# PG10__MCU.net
KiCad netlist of a schematic drawn in Altium Designer
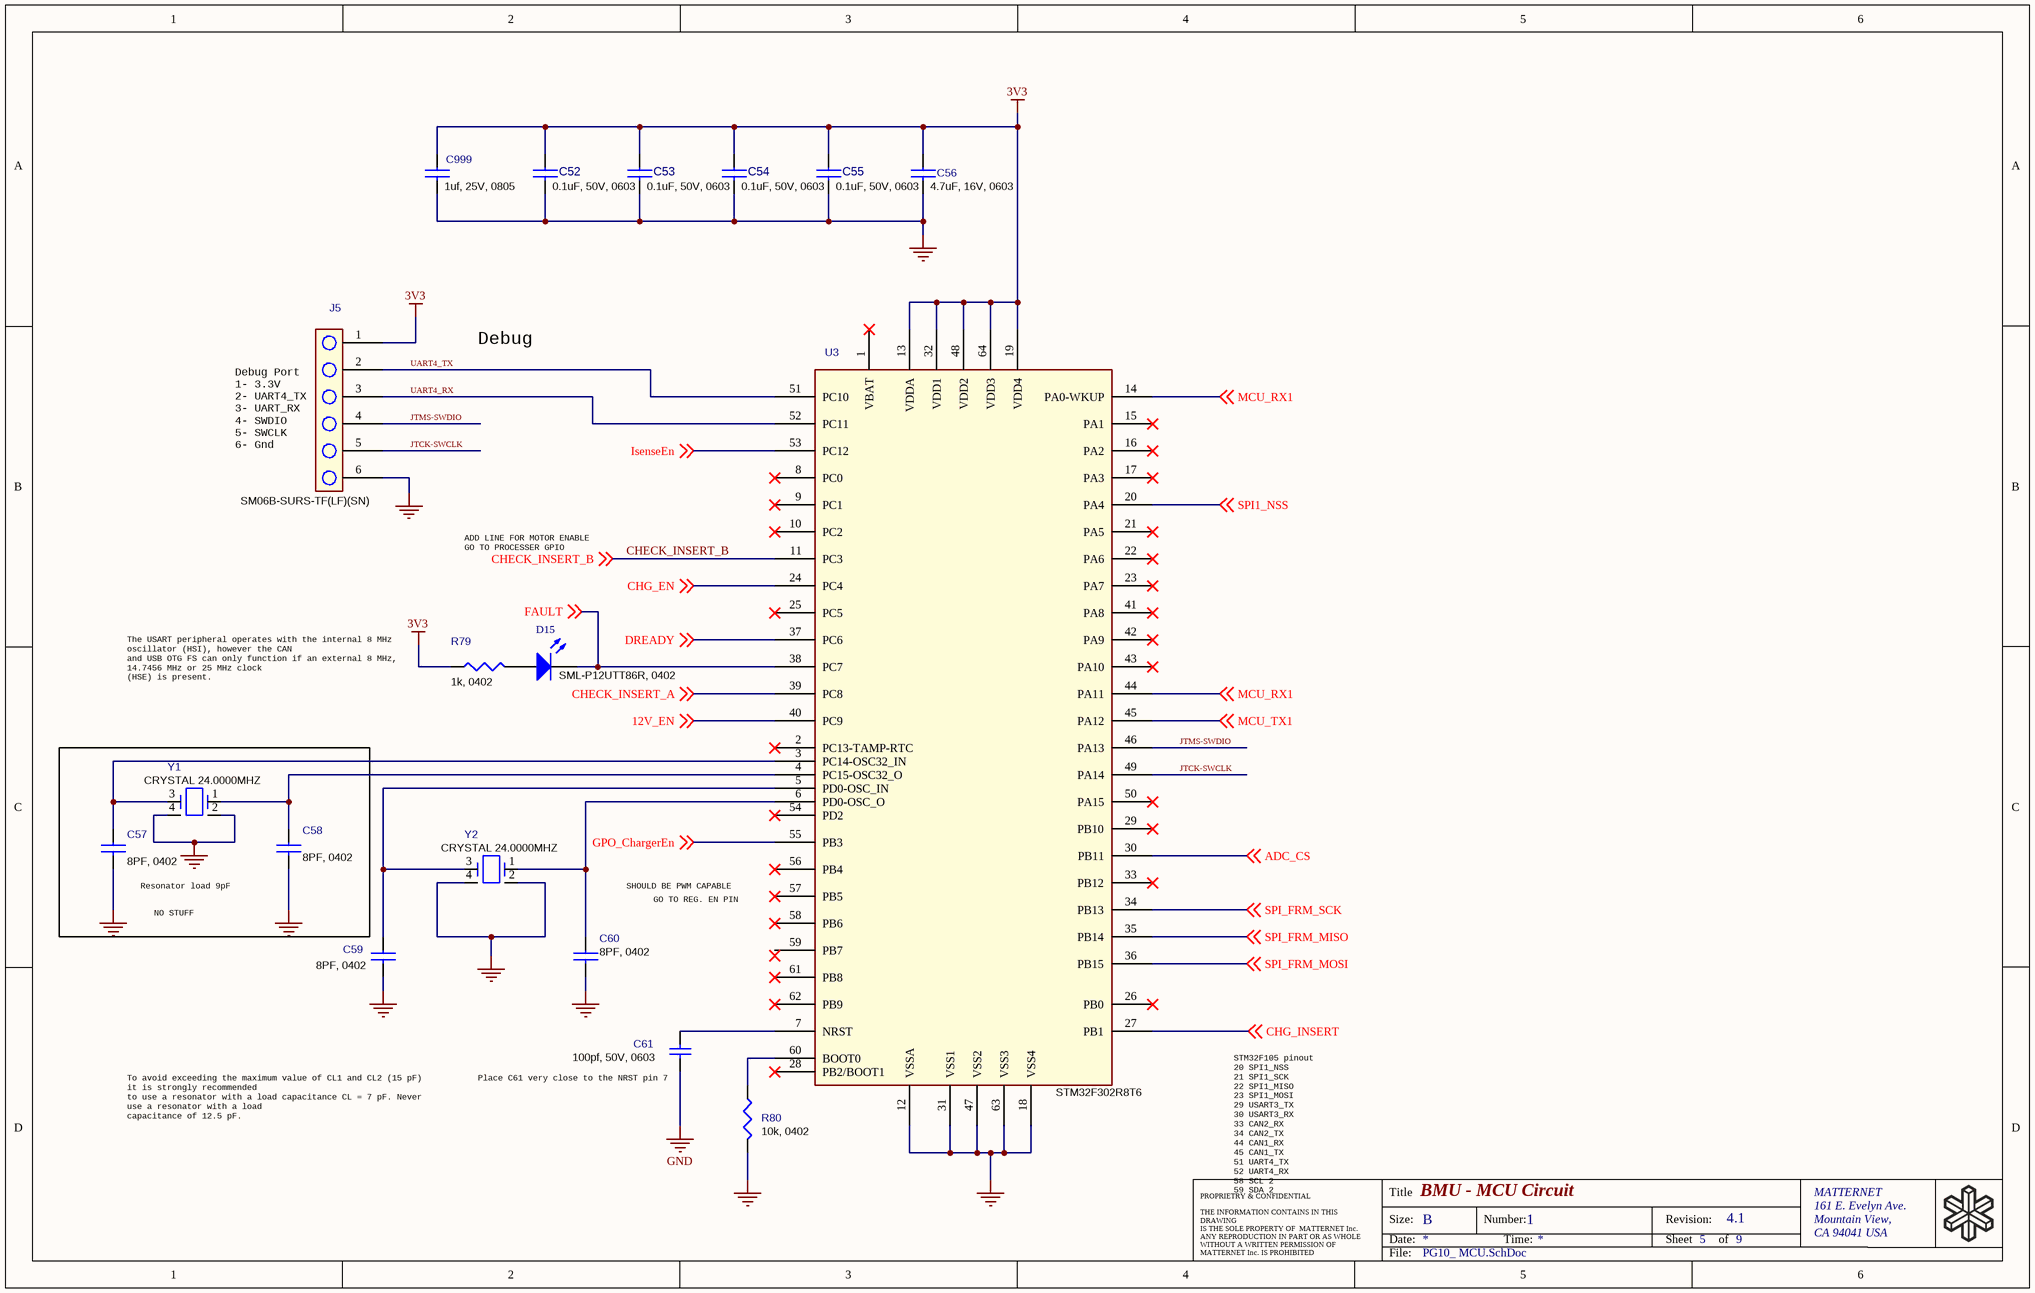
[diagram p0: PG10_ MCU.SchDoc]

(export (version "E")
  (design (tool "Eeschema 10.0.6"))
  (components
    (comp (ref "C52")
      (value "0.1uF, 50V, 0603")
      (footprint "C0603")
      (description "CAP CER 0.1UF 50V 10% X7R 0603")
      (fields
        (field (name "MANUFACTURER") "Murata")
        (field (name "MANUFACTURER PART NUMBER") "GCJ188R71E104KA12D")
      )
      (libsource (lib "*") (part "CAP-Generic-0603"))
    )
    (comp (ref "C53")
      (value "0.1uF, 50V, 0603")
      (footprint "C0603")
      (description "CAP CER 0.1UF 50V 10% X7R 0603")
      (fields
        (field (name "MANUFACTURER") "Murata")
        (field (name "MANUFACTURER PART NUMBER") "GCJ188R71E104KA12D")
      )
      (libsource (lib "*") (part "CAP-Generic-0603"))
    )
    (comp (ref "C54")
      (value "0.1uF, 50V, 0603")
      (footprint "C0603")
      (description "CAP CER 0.1UF 50V 10% X7R 0603")
      (fields
        (field (name "MANUFACTURER") "Murata")
        (field (name "MANUFACTURER PART NUMBER") "GCJ188R71E104KA12D")
      )
      (libsource (lib "*") (part "CAP-Generic-0603"))
    )
    (comp (ref "C55")
      (value "0.1uF, 50V, 0603")
      (footprint "C0603")
      (description "CAP CER 0.1UF 50V 10% X7R 0603")
      (fields
        (field (name "MANUFACTURER") "Murata")
        (field (name "MANUFACTURER PART NUMBER") "GCJ188R71E104KA12D")
      )
      (libsource (lib "*") (part "CAP-Generic-0603"))
    )
    (comp (ref "C56")
      (value "4.7uF, 16V, 0603")
      (footprint "C0805")
      (description "CAP CER 4.7UF 16V 10% X7R 0805")
      (fields
        (field (name "MANUFACTURER") "TDK")
        (field (name "MANUFACTURER PART NUMBER") "CGA4J3X7R1C475K125AE")
      )
      (libsource (lib "*") (part "CAP-Generic-0603"))
    )
    (comp (ref "C57")
      (value "8PF, 0402")
      (footprint "C0402")
      (description "CAP CER 8PF 50V C0G 0402")
      (fields
        (field (name "MANUFACTURER") "TDK")
        (field (name "MANUFACTURER PART NUMBER") "CGA2B2C0G1H080D050BA")
      )
      (libsource (lib "*") (part "CAP-Generic-0402"))
    )
    (comp (ref "C58")
      (value "8PF, 0402")
      (footprint "C0402")
      (description "CAP CER 8PF 50V C0G 0402")
      (fields
        (field (name "MANUFACTURER") "TDK")
        (field (name "MANUFACTURER PART NUMBER") "CGA2B2C0G1H080D050BA")
      )
      (libsource (lib "*") (part "CAP-Generic-0402"))
    )
    (comp (ref "C59")
      (value "8PF, 0402")
      (footprint "C0402")
      (description "CAP CER 8PF 50V C0G 0402")
      (fields
        (field (name "MANUFACTURER") "TDK")
        (field (name "MANUFACTURER PART NUMBER") "CGA2B2C0G1H080D050BA")
      )
      (libsource (lib "*") (part "CAP-Generic-0402"))
    )
    (comp (ref "C60")
      (value "8PF, 0402")
      (footprint "C0402")
      (description "CAP CER 8PF 50V C0G 0402")
      (fields
        (field (name "MANUFACTURER") "TDK")
        (field (name "MANUFACTURER PART NUMBER") "CGA2B2C0G1H080D050BA")
      )
      (libsource (lib "*") (part "CAP-Generic-0402"))
    )
    (comp (ref "C61")
      (value "100pf, 50V, 0603")
      (footprint "C0603")
      (description "CAP CER 100PF 50V NP0 0603")
      (fields
        (field (name "MANUFACTURER") "TDK")
        (field (name "MANUFACTURER PART NUMBER") "CGA3E2C0G1H101J080AE")
      )
      (libsource (lib "Miscellaneous Devices") (part "Cap"))
    )
    (comp (ref "C999")
      (value "1uf, 25V, 0805")
      (footprint "C0805")
      (description "CAP CER 1UF 25V X7R 0805")
      (fields
        (field (name "MANUFACTURER") "Murata")
        (field (name "MANUFACTURER PART NUMBER") "GCJ21BR71E105KA12L")
      )
      (libsource (lib "*") (part "CAP-Generic-0402"))
    )
    (comp (ref "D15")
      (value "SML-P12UTT86R, 0402")
      (footprint "D0402_1")
      (description "LED Uni-Color Red Chip LED 2-Pin 0402 T/R")
      (fields (field (name "MANUFACTURER") "Rohm") (field (name "MANUFACTURER PART NUMBER") "SML-P12U2TT86R"))
      (libsource (lib "Miscellaneous Devices") (part "LED0"))
    )
    (comp (ref "J5")
      (value "SM06B-SURS-TF(LF)(SN)")
      (footprint "0.8mm")
      (description "Headers & Wire Housings 6P SR UNSHRD HRD TIN OVER NI")
      (fields (field (name "MANUFACTURER") "JST"))
      (libsource (lib "*") (part "CONN-GENERIC-1X6"))
    )
    (comp (ref "R79")
      (value "1k, 0402")
      (footprint "R0402")
      (description "RES SMD 1K OHM 5% 1/16W 0402")
      (fields
        (field (name "MANUFACTURER") "Yageo")
        (field (name "MANUFACTURER PART NUMBER") "RC0402JR-071KL")
      )
      (libsource (lib "*") (part "R-Generic-0402"))
    )
    (comp (ref "R80")
      (value "10k, 0402")
      (footprint "R0402")
      (description "RES SMD 10K OHM 1% 1/16W 0402")
      (fields
        (field (name "MANUFACTURER") "Vishay Dale")
        (field (name "MANUFACTURER PART NUMBER") "CRCW040210K0FKTD")
      )
      (libsource (lib "Miscellaneous Devices") (part "R-Generic-0402"))
    )
    (comp (ref "U3")
      (value "STM32F302R8T6")
      (footprint "64LQFP")
      (description "MCU 32-bit STM32 ARM Cortex M4 RISC 128KB Flash 2.5V/3.3V 64-Pin LQFP Tray")
      (libsource (lib "*") (part "MCU-STM32F105RBT6-700-443"))
    )
    (comp (ref "Y1")
      (value "CRYSTAL 24.0000MHZ")
      (footprint "CRYSTAL_NX3225SA")
      (description "CRYSTAL 24.0000MHZ 8PF SMD")
      (fields
        (field (name "MANUFACTURER") "NDK")
        (field (name "MANUFACTURER PART NUMBER") "NX3225SA-24.000MHZ-STD-CSR-1")
      )
      (libsource (lib "*") (part "CRY-Generic"))
    )
    (comp (ref "Y2")
      (value "CRYSTAL 24.0000MHZ")
      (footprint "CRYSTAL_NX3225SA")
      (description "CRYSTAL 24.0000MHZ 8PF SMD")
      (fields
        (field (name "MANUFACTURER") "NDK")
        (field (name "MANUFACTURER PART NUMBER") "NX3225SA-24.000MHZ-STD-CSR-1")
      )
      (libsource (lib "*") (part "CRY-Generic"))
    )
  )
  (nets
    (net (code "1") (name "/JTCK-SWCLK") (class "Default")
      (node (ref "J5") (pin "5") (pinfunction "5_5") (pintype "passive"))
      (node (ref "U3") (pin "49") (pinfunction "PA14_49") (pintype "passive"))
    )
    (net (code "2") (name "/JTMS-SWDIO") (class "Default")
      (node (ref "J5") (pin "4") (pinfunction "4_4") (pintype "passive"))
      (node (ref "U3") (pin "46") (pinfunction "PA13_46") (pintype "passive"))
    )
    (net (code "3") (name "/UART4_RX") (class "Default")
      (node (ref "J5") (pin "3") (pinfunction "3_3") (pintype "passive"))
      (node (ref "U3") (pin "52") (pinfunction "PC11_52") (pintype "passive"))
    )
    (net (code "4") (name "/UART4_TX") (class "Default")
      (node (ref "J5") (pin "2") (pinfunction "2_2") (pintype "passive"))
      (node (ref "U3") (pin "51") (pinfunction "PC10_51") (pintype "passive"))
    )
    (net (code "5") (name "3V3") (class "Default")
      (node (ref "C52") (pin "1") (pinfunction "1_1") (pintype "passive"))
      (node (ref "C53") (pin "1") (pinfunction "1_1") (pintype "passive"))
      (node (ref "C54") (pin "1") (pinfunction "1_1") (pintype "passive"))
      (node (ref "C55") (pin "1") (pinfunction "1_1") (pintype "passive"))
      (node (ref "C56") (pin "1") (pinfunction "1_1") (pintype "passive"))
      (node (ref "C999") (pin "1") (pinfunction "1_1") (pintype "passive"))
      (node (ref "J5") (pin "1") (pinfunction "1_1") (pintype "passive"))
      (node (ref "R79") (pin "1") (pinfunction "1_1") (pintype "passive"))
      (node (ref "U3") (pin "13") (pinfunction "VDDA_13") (pintype "passive"))
      (node (ref "U3") (pin "19") (pinfunction "VDD4_19") (pintype "passive"))
      (node (ref "U3") (pin "32") (pinfunction "VDD1_32") (pintype "passive"))
      (node (ref "U3") (pin "48") (pinfunction "VDD2_48") (pintype "passive"))
      (node (ref "U3") (pin "64") (pinfunction "VDD3_64") (pintype "passive"))
    )
    (net (code "6") (name "12V_EN") (class "Default")
      (node (ref "U3") (pin "40") (pinfunction "PC9_40") (pintype "passive"))
    )
    (net (code "7") (name "ADC_CS") (class "Default")
      (node (ref "U3") (pin "30") (pinfunction "PB11_30") (pintype "passive"))
    )
    (net (code "8") (name "CHECK_INSERT_A") (class "Default")
      (node (ref "U3") (pin "39") (pinfunction "PC8_39") (pintype "passive"))
    )
    (net (code "9") (name "CHECK_INSERT_B") (class "Default")
      (node (ref "U3") (pin "11") (pinfunction "PC3_11") (pintype "passive"))
    )
    (net (code "10") (name "CHG_EN") (class "Default")
      (node (ref "U3") (pin "24") (pinfunction "PC4_24") (pintype "passive"))
    )
    (net (code "11") (name "CHG_INSERT") (class "Default")
      (node (ref "U3") (pin "27") (pinfunction "PB1_27") (pintype "passive"))
    )
    (net (code "12") (name "DREADY") (class "Default")
      (node (ref "U3") (pin "37") (pinfunction "PC6_37") (pintype "passive"))
    )
    (net (code "13") (name "FAULT") (class "Default")
      (node (ref "D15") (pin "2") (pinfunction "K_2") (pintype "passive"))
      (node (ref "U3") (pin "38") (pinfunction "PC7_38") (pintype "passive"))
    )
    (net (code "14") (name "GND") (class "Default")
      (node (ref "C52") (pin "2") (pinfunction "2_2") (pintype "passive"))
      (node (ref "C53") (pin "2") (pinfunction "2_2") (pintype "passive"))
      (node (ref "C54") (pin "2") (pinfunction "2_2") (pintype "passive"))
      (node (ref "C55") (pin "2") (pinfunction "2_2") (pintype "passive"))
      (node (ref "C56") (pin "2") (pinfunction "2_2") (pintype "passive"))
      (node (ref "C57") (pin "2") (pinfunction "2_2") (pintype "passive"))
      (node (ref "C58") (pin "2") (pinfunction "2_2") (pintype "passive"))
      (node (ref "C59") (pin "2") (pinfunction "2_2") (pintype "passive"))
      (node (ref "C60") (pin "2") (pinfunction "2_2") (pintype "passive"))
      (node (ref "C61") (pin "1") (pinfunction "1_1") (pintype "passive"))
      (node (ref "C999") (pin "2") (pinfunction "2_2") (pintype "passive"))
      (node (ref "J5") (pin "6") (pinfunction "6_6") (pintype "passive"))
      (node (ref "R80") (pin "2") (pinfunction "2_2") (pintype "passive"))
      (node (ref "U3") (pin "12") (pinfunction "VSSA_12") (pintype "passive"))
      (node (ref "U3") (pin "18") (pinfunction "VSS4_18") (pintype "passive"))
      (node (ref "U3") (pin "31") (pinfunction "VSS1_31") (pintype "passive"))
      (node (ref "U3") (pin "47") (pinfunction "VSS2_47") (pintype "passive"))
      (node (ref "U3") (pin "63") (pinfunction "VSS3_63") (pintype "passive"))
      (node (ref "Y1") (pin "2") (pinfunction "2_2") (pintype "passive"))
      (node (ref "Y1") (pin "4") (pinfunction "4_4") (pintype "passive"))
      (node (ref "Y2") (pin "2") (pinfunction "2_2") (pintype "passive"))
      (node (ref "Y2") (pin "4") (pinfunction "4_4") (pintype "passive"))
    )
    (net (code "15") (name "GPO_ChargerEn") (class "Default")
      (node (ref "U3") (pin "55") (pinfunction "PB3_55") (pintype "passive"))
    )
    (net (code "16") (name "IsenseEn") (class "Default")
      (node (ref "U3") (pin "53") (pinfunction "PC12_53") (pintype "passive"))
    )
    (net (code "17") (name "MCU_RX1") (class "Default")
      (node (ref "U3") (pin "14") (pinfunction "PA0-WKUP_14") (pintype "passive"))
      (node (ref "U3") (pin "44") (pinfunction "PA11_44") (pintype "passive"))
    )
    (net (code "18") (name "MCU_TX1") (class "Default")
      (node (ref "U3") (pin "45") (pinfunction "PA12_45") (pintype "passive"))
    )
    (net (code "19") (name "Net-(U3-BOOT0)") (class "Default")
      (node (ref "R80") (pin "1") (pinfunction "1_1") (pintype "passive"))
      (node (ref "U3") (pin "60") (pinfunction "BOOT0_60") (pintype "passive"))
    )
    (net (code "20") (name "Net-(U3-NRST)") (class "Default")
      (node (ref "C61") (pin "2") (pinfunction "2_2") (pintype "passive"))
      (node (ref "U3") (pin "7") (pinfunction "NRST_7") (pintype "passive"))
    )
    (net (code "21") (name "Net-(U3-PC14-OSC32_IN)") (class "Default")
      (node (ref "C57") (pin "1") (pinfunction "1_1") (pintype "passive"))
      (node (ref "U3") (pin "3") (pinfunction "PC14-OSC32_IN_3") (pintype "passive"))
      (node (ref "Y1") (pin "3") (pinfunction "3_3") (pintype "passive"))
    )
    (net (code "22") (name "Net-(U3-PC15-OSC32_O)") (class "Default")
      (node (ref "C58") (pin "1") (pinfunction "1_1") (pintype "passive"))
      (node (ref "U3") (pin "4") (pinfunction "PC15-OSC32_O_4") (pintype "passive"))
      (node (ref "Y1") (pin "1") (pinfunction "1_1") (pintype "passive"))
    )
    (net (code "23") (name "Net-(U3-PD0-OSC_IN)") (class "Default")
      (node (ref "C59") (pin "1") (pinfunction "1_1") (pintype "passive"))
      (node (ref "U3") (pin "5") (pinfunction "PD0-OSC_IN_5") (pintype "passive"))
      (node (ref "Y2") (pin "3") (pinfunction "3_3") (pintype "passive"))
    )
    (net (code "24") (name "Net-(U3-PD0-OSC_O)") (class "Default")
      (node (ref "C60") (pin "1") (pinfunction "1_1") (pintype "passive"))
      (node (ref "U3") (pin "6") (pinfunction "PD0-OSC_O_6") (pintype "passive"))
      (node (ref "Y2") (pin "1") (pinfunction "1_1") (pintype "passive"))
    )
    (net (code "25") (name "SPI1_NSS") (class "Default")
      (node (ref "U3") (pin "20") (pinfunction "PA4_20") (pintype "passive"))
    )
    (net (code "26") (name "SPI_FRM_MISO") (class "Default")
      (node (ref "U3") (pin "35") (pinfunction "PB14_35") (pintype "passive"))
    )
    (net (code "27") (name "SPI_FRM_MOSI") (class "Default")
      (node (ref "U3") (pin "36") (pinfunction "PB15_36") (pintype "passive"))
    )
    (net (code "28") (name "SPI_FRM_SCK") (class "Default")
      (node (ref "U3") (pin "34") (pinfunction "PB13_34") (pintype "passive"))
    )
    (net (code "29") (name "unconnected-(D15-A-Pad1)") (class "Default")
      (node (ref "D15") (pin "1") (pinfunction "A_1") (pintype "passive"))
    )
    (net (code "30") (name "unconnected-(R79-Pad2)") (class "Default")
      (node (ref "R79") (pin "2") (pinfunction "2_2") (pintype "passive"))
    )
    (net (code "31") (name "unconnected-(U3-PA1-Pad15)") (class "Default")
      (node (ref "U3") (pin "15") (pinfunction "PA1_15") (pintype "passive+no_connect"))
    )
    (net (code "32") (name "unconnected-(U3-PA2-Pad16)") (class "Default")
      (node (ref "U3") (pin "16") (pinfunction "PA2_16") (pintype "passive+no_connect"))
    )
    (net (code "33") (name "unconnected-(U3-PA3-Pad17)") (class "Default")
      (node (ref "U3") (pin "17") (pinfunction "PA3_17") (pintype "passive+no_connect"))
    )
    (net (code "34") (name "unconnected-(U3-PA5-Pad21)") (class "Default")
      (node (ref "U3") (pin "21") (pinfunction "PA5_21") (pintype "passive+no_connect"))
    )
    (net (code "35") (name "unconnected-(U3-PA6-Pad22)") (class "Default")
      (node (ref "U3") (pin "22") (pinfunction "PA6_22") (pintype "passive+no_connect"))
    )
    (net (code "36") (name "unconnected-(U3-PA7-Pad23)") (class "Default")
      (node (ref "U3") (pin "23") (pinfunction "PA7_23") (pintype "passive+no_connect"))
    )
    (net (code "37") (name "unconnected-(U3-PA8-Pad41)") (class "Default")
      (node (ref "U3") (pin "41") (pinfunction "PA8_41") (pintype "passive+no_connect"))
    )
    (net (code "38") (name "unconnected-(U3-PA9-Pad42)") (class "Default")
      (node (ref "U3") (pin "42") (pinfunction "PA9_42") (pintype "passive+no_connect"))
    )
    (net (code "39") (name "unconnected-(U3-PA10-Pad43)") (class "Default")
      (node (ref "U3") (pin "43") (pinfunction "PA10_43") (pintype "passive+no_connect"))
    )
    (net (code "40") (name "unconnected-(U3-PA15-Pad50)") (class "Default")
      (node (ref "U3") (pin "50") (pinfunction "PA15_50") (pintype "passive+no_connect"))
    )
    (net (code "41") (name "unconnected-(U3-PB0-Pad26)") (class "Default")
      (node (ref "U3") (pin "26") (pinfunction "PB0_26") (pintype "passive+no_connect"))
    )
    (net (code "42") (name "unconnected-(U3-PB2{slash}BOOT1-Pad28)") (class "Default")
      (node (ref "U3") (pin "28") (pinfunction "PB2/BOOT1_28") (pintype "passive+no_connect"))
    )
    (net (code "43") (name "unconnected-(U3-PB4-Pad56)") (class "Default")
      (node (ref "U3") (pin "56") (pinfunction "PB4_56") (pintype "passive+no_connect"))
    )
    (net (code "44") (name "unconnected-(U3-PB5-Pad57)") (class "Default")
      (node (ref "U3") (pin "57") (pinfunction "PB5_57") (pintype "passive+no_connect"))
    )
    (net (code "45") (name "unconnected-(U3-PB6-Pad58)") (class "Default")
      (node (ref "U3") (pin "58") (pinfunction "PB6_58") (pintype "passive+no_connect"))
    )
    (net (code "46") (name "unconnected-(U3-PB7-Pad59)") (class "Default")
      (node (ref "U3") (pin "59") (pinfunction "PB7_59") (pintype "passive"))
    )
    (net (code "47") (name "unconnected-(U3-PB8-Pad61)") (class "Default")
      (node (ref "U3") (pin "61") (pinfunction "PB8_61") (pintype "passive+no_connect"))
    )
    (net (code "48") (name "unconnected-(U3-PB9-Pad62)") (class "Default")
      (node (ref "U3") (pin "62") (pinfunction "PB9_62") (pintype "passive+no_connect"))
    )
    (net (code "49") (name "unconnected-(U3-PB10-Pad29)") (class "Default")
      (node (ref "U3") (pin "29") (pinfunction "PB10_29") (pintype "passive+no_connect"))
    )
    (net (code "50") (name "unconnected-(U3-PB12-Pad33)") (class "Default")
      (node (ref "U3") (pin "33") (pinfunction "PB12_33") (pintype "passive+no_connect"))
    )
    (net (code "51") (name "unconnected-(U3-PC0-Pad8)") (class "Default")
      (node (ref "U3") (pin "8") (pinfunction "PC0_8") (pintype "passive+no_connect"))
    )
    (net (code "52") (name "unconnected-(U3-PC1-Pad9)") (class "Default")
      (node (ref "U3") (pin "9") (pinfunction "PC1_9") (pintype "passive+no_connect"))
    )
    (net (code "53") (name "unconnected-(U3-PC2-Pad10)") (class "Default")
      (node (ref "U3") (pin "10") (pinfunction "PC2_10") (pintype "passive+no_connect"))
    )
    (net (code "54") (name "unconnected-(U3-PC5-Pad25)") (class "Default")
      (node (ref "U3") (pin "25") (pinfunction "PC5_25") (pintype "passive+no_connect"))
    )
    (net (code "55") (name "unconnected-(U3-PC13-TAMP-RTC-Pad2)") (class "Default")
      (node (ref "U3") (pin "2") (pinfunction "PC13-TAMP-RTC_2") (pintype "passive+no_connect"))
    )
    (net (code "56") (name "unconnected-(U3-PD2-Pad54)") (class "Default")
      (node (ref "U3") (pin "54") (pinfunction "PD2_54") (pintype "passive+no_connect"))
    )
    (net (code "57") (name "unconnected-(U3-VBAT-Pad1)") (class "Default")
      (node (ref "U3") (pin "1") (pinfunction "VBAT_1") (pintype "passive+no_connect"))
    )
  )
)
